# LiDAR_Lite_Interface.net
KiCad netlist of a schematic drawn in EAGLE
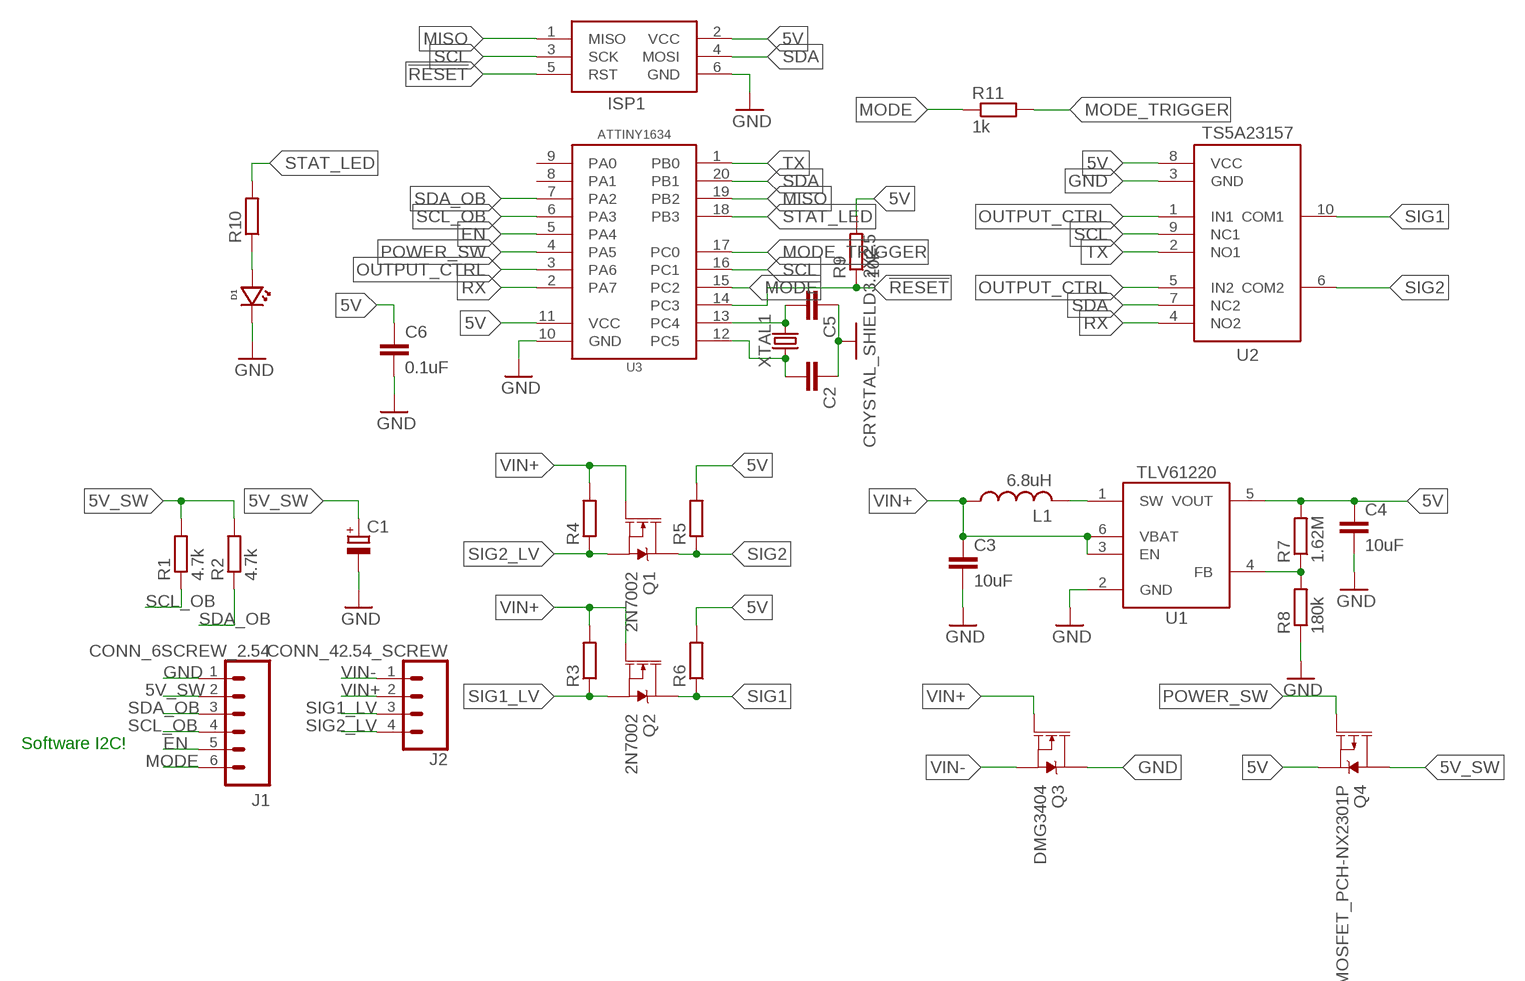
[diagram p0: schematic, sheet 1]

(export (version "E")
  (design (tool "Eeschema 10.0.6"))
  (components
    (comp (ref "C1")
      (value "CPOL-EUUW-10X10")
      (footprint "eagle-import:UW-10X10_NICHICON")
      (libsource (lib "eagle-import") (part "CPOL-EUUW-10X10"))
    )
    (comp (ref "C2")
      (value "C-EU10PFC0603")
      (footprint "eagle-import:C0603")
      (fields (field (name "MF") "Yageo") (field (name "MPN") "CC0603JRNPO9BN100CC0603JRNPO9BN100"))
      (libsource (lib "eagle-import") (part "C-EUC060310PF"))
    )
    (comp (ref "C3")
      (value "10uF")
      (footprint "eagle-import:C0805")
      (fields (field (name "MF") "Murata") (field (name "MPN") "GRM21BR61C106KE15K"))
      (libsource (lib "eagle-import") (part "C-EUC080510UF"))
    )
    (comp (ref "C4")
      (value "10uF")
      (footprint "eagle-import:C0805")
      (fields (field (name "MF") "Murata") (field (name "MPN") "GRM21BR61C106KE15K"))
      (libsource (lib "eagle-import") (part "C-EUC080510UF"))
    )
    (comp (ref "C5")
      (value "C-EU10PFC0603")
      (footprint "eagle-import:C0603")
      (fields (field (name "MF") "Yageo") (field (name "MPN") "CC0603JRNPO9BN100CC0603JRNPO9BN100"))
      (libsource (lib "eagle-import") (part "C-EUC060310PF"))
    )
    (comp (ref "C6")
      (value "0.1uF")
      (footprint "eagle-import:C0603")
      (fields (field (name "MF") "Murata") (field (name "MPN") "GCM188R71E104KA57D"))
      (libsource (lib "eagle-import") (part "C-EUC06030.1UF"))
    )
    (comp (ref "D1")
      (value "LED0603")
      (footprint "eagle-import:LED_0603")
      (libsource (lib "eagle-import") (part "LED0603"))
    )
    (comp (ref "ISP1")
      (value "AVRISP-6")
      (footprint "eagle-import:AVRISP")
      (libsource (lib "eagle-import") (part "AVRISP-6"))
    )
    (comp (ref "J1")
      (value "CONN_6SCREW_2.54")
      (footprint "eagle-import:1X06_SCREW")
      (fields (field (name "MF") "OnShore") (field (name "MPN") "OSTVN06A150"))
      (libsource (lib "eagle-import") (part "CONN_6SCREW_2.54"))
    )
    (comp (ref "J2")
      (value "CONN_42.54_SCREW")
      (footprint "eagle-import:1X04_SCREW")
      (fields (field (name "MF") "On Shore") (field (name "MPN") "OSTVN04A150"))
      (libsource (lib "eagle-import") (part "CONN_42.54_SCREW"))
    )
    (comp (ref "L1")
      (value "6.8uH")
      (footprint "eagle-import:1008")
      (fields (field (name "MF") "Wurth") (field (name "MPN") "74438323068"))
      (libsource (lib "eagle-import") (part "INDUCTOR1008"))
    )
    (comp (ref "Q1")
      (value "2N7002")
      (footprint "eagle-import:SOT23-3")
      (fields (field (name "MF") "Nexperia") (field (name "MPN") "2N7002P,215"))
      (libsource (lib "eagle-import") (part "MOSFET-NCH-2N7002P"))
    )
    (comp (ref "Q2")
      (value "2N7002")
      (footprint "eagle-import:SOT23-3")
      (fields (field (name "MF") "Nexperia") (field (name "MPN") "2N7002P,215"))
      (libsource (lib "eagle-import") (part "MOSFET-NCH-2N7002P"))
    )
    (comp (ref "Q3")
      (value "DMG3404")
      (footprint "eagle-import:SOT23-3")
      (fields (field (name "MF") "Diodes Incorporated") (field (name "MPN") "DMG3404L-7"))
      (libsource (lib "eagle-import") (part "MOSFET-NCH-DMG3404L"))
    )
    (comp (ref "Q4")
      (value "MOSFET_PCH-NX2301P")
      (footprint "eagle-import:SOT23-3")
      (fields (field (name "MF") "Nexperia") (field (name "MPN") "NX2301P,215"))
      (libsource (lib "eagle-import") (part "MOSFET_PCH-NX2301P"))
    )
    (comp (ref "R1")
      (value "4.7k")
      (footprint "eagle-import:R0603")
      (fields (field (name "MF") "Yageo") (field (name "MPN") "RC0603FR-074K7L"))
      (libsource (lib "eagle-import") (part "R-EU_R06034.7K"))
    )
    (comp (ref "R2")
      (value "4.7k")
      (footprint "eagle-import:R0603")
      (fields (field (name "MF") "Yageo") (field (name "MPN") "RC0603FR-074K7L"))
      (libsource (lib "eagle-import") (part "R-EU_R06034.7K"))
    )
    (comp (ref "R3")
      (value "R-EU_10KR0603")
      (footprint "eagle-import:R0603")
      (fields
        (field (name "MF") "Yageo")
        (field (name "MPN") "RC0603FR-0710KL")
        (field (name "VALUE_PART") "10k")
      )
      (libsource (lib "eagle-import") (part "R-EU_R060310K"))
    )
    (comp (ref "R4")
      (value "R-EU_10KR0603")
      (footprint "eagle-import:R0603")
      (fields
        (field (name "MF") "Yageo")
        (field (name "MPN") "RC0603FR-0710KL")
        (field (name "VALUE_PART") "10k")
      )
      (libsource (lib "eagle-import") (part "R-EU_R060310K"))
    )
    (comp (ref "R5")
      (value "R-EU_10KR0603")
      (footprint "eagle-import:R0603")
      (fields
        (field (name "MF") "Yageo")
        (field (name "MPN") "RC0603FR-0710KL")
        (field (name "VALUE_PART") "10k")
      )
      (libsource (lib "eagle-import") (part "R-EU_R060310K"))
    )
    (comp (ref "R6")
      (value "R-EU_10KR0603")
      (footprint "eagle-import:R0603")
      (fields
        (field (name "MF") "Yageo")
        (field (name "MPN") "RC0603FR-0710KL")
        (field (name "VALUE_PART") "10k")
      )
      (libsource (lib "eagle-import") (part "R-EU_R060310K"))
    )
    (comp (ref "R7")
      (value "1.62M")
      (footprint "eagle-import:R0603")
      (fields (field (name "MF") "Stackpole") (field (name "MPN") "RMCF0603FT1M62"))
      (libsource (lib "eagle-import") (part "R-EU_R06031.62M"))
    )
    (comp (ref "R8")
      (value "180k")
      (footprint "eagle-import:R0603")
      (fields (field (name "MF") "Panasonic") (field (name "MPN") "ERJ-3EKF1803V"))
      (libsource (lib "eagle-import") (part "R-EU_R0603180K"))
    )
    (comp (ref "R9")
      (value "10k")
      (footprint "eagle-import:R0603")
      (fields (field (name "MF") "Yageo") (field (name "MPN") "RC0603FR-0710KL"))
      (libsource (lib "eagle-import") (part "R-EU_R060310K"))
    )
    (comp (ref "R10")
      (value "R-EU_330R0603")
      (footprint "eagle-import:R0603")
      (fields
        (field (name "MF") "Yageo")
        (field (name "MPN") "RC0603FR-07330RL")
        (field (name "VALUE_PART") "330")
      )
      (libsource (lib "eagle-import") (part "R-EU_R0603330"))
    )
    (comp (ref "R11")
      (value "1k")
      (footprint "eagle-import:R0603")
      (fields (field (name "MF") "Yageo") (field (name "MPN") "AC0603FR-071KL"))
      (libsource (lib "eagle-import") (part "R-EU_R06031K"))
    )
    (comp (ref "U1")
      (value "TLV61220DBV")
      (footprint "eagle-import:DBV_R-PDSO-G6")
      (fields (field (name "MF") "TI") (field (name "MPN") "TLV61220DBVR"))
      (libsource (lib "eagle-import") (part "TLV61220DBV"))
    )
    (comp (ref "U2")
      (value "TS5A23157DGS")
      (footprint "eagle-import:DGS0010A")
      (fields (field (name "DISP") "TS5A23157") (field (name "MF") "TI") (field (name "MPN") "TS5A23157DGSR"))
      (libsource (lib "eagle-import") (part "TS5A23157DGS"))
    )
    (comp (ref "U3")
      (value "ATTINY1634SOIC")
      (footprint "eagle-import:SO-20DW")
      (fields (field (name "MF") "Atmel") (field (name "MPN") "ATTINY1634-SUR"))
      (libsource (lib "eagle-import") (part "ATTINY1634SOIC"))
    )
    (comp (ref "XTAL1")
      (value "CRYSTAL_SHIELD3.2X2.5")
      (footprint "eagle-import:CRYSTAL_3.2X2.5_4-SMD")
      (fields (field (name "MF") "Abricon") (field (name "MPN") "ABM8G-12.000MHZ-4Y-T3"))
      (libsource (lib "eagle-import") (part "CRYSTAL_SHIELD3.2X2.5"))
    )
  )
  (nets
    (net (code "1") (name "/~{RESET}") (class "Default")
      (node (ref "ISP1") (pin "5") (pinfunction "RST_5") (pintype "output"))
      (node (ref "R9") (pin "1") (pinfunction "1_1") (pintype "passive"))
      (node (ref "U3") (pin "14") (pinfunction "PC3_14") (pintype "bidirectional"))
    )
    (net (code "2") (name "5V") (class "Default")
      (node (ref "C4") (pin "1") (pinfunction "1_1") (pintype "passive"))
      (node (ref "C6") (pin "1") (pinfunction "1_1") (pintype "passive"))
      (node (ref "ISP1") (pin "2") (pinfunction "VCC_2") (pintype "power_in"))
      (node (ref "Q4") (pin "2") (pinfunction "S_2") (pintype "bidirectional"))
      (node (ref "R5") (pin "2") (pinfunction "2_2") (pintype "passive"))
      (node (ref "R6") (pin "2") (pinfunction "2_2") (pintype "passive"))
      (node (ref "R7") (pin "2") (pinfunction "2_2") (pintype "passive"))
      (node (ref "R9") (pin "2") (pinfunction "2_2") (pintype "passive"))
      (node (ref "U1") (pin "5") (pinfunction "VOUT_5") (pintype "power_in"))
      (node (ref "U2") (pin "8") (pinfunction "VCC_8") (pintype "power_in"))
      (node (ref "U3") (pin "11") (pinfunction "VCC_11") (pintype "power_in"))
    )
    (net (code "3") (name "5V_SW") (class "Default")
      (node (ref "C1") (pin "+") (pinfunction "+_+") (pintype "passive"))
      (node (ref "J1") (pin "2") (pinfunction "2_2") (pintype "passive"))
      (node (ref "Q4") (pin "3") (pinfunction "D_3") (pintype "bidirectional"))
      (node (ref "R1") (pin "2") (pinfunction "2_2") (pintype "passive"))
      (node (ref "R2") (pin "2") (pinfunction "2_2") (pintype "passive"))
    )
    (net (code "4") (name "EN") (class "Default")
      (node (ref "J1") (pin "5") (pinfunction "5_5") (pintype "passive"))
      (node (ref "U3") (pin "5") (pinfunction "PA4_5") (pintype "bidirectional"))
    )
    (net (code "5") (name "GND") (class "Default")
      (node (ref "C1") (pin "-") (pinfunction "-_-") (pintype "passive"))
      (node (ref "C2") (pin "1") (pinfunction "1_1") (pintype "passive"))
      (node (ref "C3") (pin "2") (pinfunction "2_2") (pintype "passive"))
      (node (ref "C4") (pin "2") (pinfunction "2_2") (pintype "passive"))
      (node (ref "C5") (pin "1") (pinfunction "1_1") (pintype "passive"))
      (node (ref "C6") (pin "2") (pinfunction "2_2") (pintype "passive"))
      (node (ref "D1") (pin "CATHODE") (pinfunction "CATHODE_CATHODE") (pintype "power_in"))
      (node (ref "ISP1") (pin "6") (pinfunction "GND_6") (pintype "power_in"))
      (node (ref "J1") (pin "1") (pinfunction "1_1") (pintype "passive"))
      (node (ref "Q3") (pin "3") (pinfunction "D_3") (pintype "bidirectional"))
      (node (ref "R8") (pin "1") (pinfunction "1_1") (pintype "passive"))
      (node (ref "U1") (pin "2") (pinfunction "GND_2") (pintype "power_in"))
      (node (ref "U2") (pin "3") (pinfunction "GND_3") (pintype "power_in"))
      (node (ref "U3") (pin "10") (pinfunction "GND_10") (pintype "power_in"))
      (node (ref "XTAL1") (pin "2") (pinfunction "GND_2") (pintype "power_in"))
      (node (ref "XTAL1") (pin "4") (pinfunction "GND_4") (pintype "power_in"))
    )
    (net (code "6") (name "MISO") (class "Default")
      (node (ref "ISP1") (pin "1") (pinfunction "MISO_1") (pintype "input"))
      (node (ref "U3") (pin "19") (pinfunction "PB2_19") (pintype "bidirectional"))
    )
    (net (code "7") (name "MODE") (class "Default")
      (node (ref "J1") (pin "6") (pinfunction "6_6") (pintype "passive"))
      (node (ref "R11") (pin "1") (pinfunction "1_1") (pintype "passive"))
      (node (ref "U3") (pin "15") (pinfunction "PC2_15") (pintype "bidirectional"))
    )
    (net (code "8") (name "MODE_TRIGGER") (class "Default")
      (node (ref "R11") (pin "2") (pinfunction "2_2") (pintype "passive"))
      (node (ref "U3") (pin "17") (pinfunction "PC0_17") (pintype "bidirectional"))
    )
    (net (code "9") (name "Net-(D1-PadANODE)") (class "Default")
      (node (ref "D1") (pin "ANODE") (pinfunction "ANODE_ANODE") (pintype "power_in"))
      (node (ref "R10") (pin "1") (pinfunction "1_1") (pintype "passive"))
    )
    (net (code "10") (name "Net-(U1-FB)") (class "Default")
      (node (ref "R7") (pin "1") (pinfunction "1_1") (pintype "passive"))
      (node (ref "R8") (pin "2") (pinfunction "2_2") (pintype "passive"))
      (node (ref "U1") (pin "4") (pinfunction "FB_4") (pintype "input"))
    )
    (net (code "11") (name "Net-(U1-SW)") (class "Default")
      (node (ref "L1") (pin "2") (pinfunction "2_2") (pintype "passive"))
      (node (ref "U1") (pin "1") (pinfunction "SW_1") (pintype "power_in"))
    )
    (net (code "12") (name "Net-(U3-PC4)") (class "Default")
      (node (ref "C5") (pin "2") (pinfunction "2_2") (pintype "passive"))
      (node (ref "U3") (pin "13") (pinfunction "PC4_13") (pintype "bidirectional"))
      (node (ref "XTAL1") (pin "3") (pinfunction "2_3") (pintype "passive"))
    )
    (net (code "13") (name "Net-(U3-PC5)") (class "Default")
      (node (ref "C2") (pin "2") (pinfunction "2_2") (pintype "passive"))
      (node (ref "U3") (pin "12") (pinfunction "PC5_12") (pintype "bidirectional"))
      (node (ref "XTAL1") (pin "1") (pinfunction "1_1") (pintype "passive"))
    )
    (net (code "14") (name "OUTPUT_CTRL") (class "Default")
      (node (ref "U2") (pin "1") (pinfunction "IN1_1") (pintype "input"))
      (node (ref "U2") (pin "5") (pinfunction "IN2_5") (pintype "input"))
      (node (ref "U3") (pin "3") (pinfunction "PA6_3") (pintype "bidirectional"))
    )
    (net (code "15") (name "POWER_SW") (class "Default")
      (node (ref "Q4") (pin "1") (pinfunction "G_1") (pintype "bidirectional"))
      (node (ref "U3") (pin "4") (pinfunction "PA5_4") (pintype "bidirectional"))
    )
    (net (code "16") (name "RX") (class "Default")
      (node (ref "U2") (pin "4") (pinfunction "NO2_4") (pintype "bidirectional"))
      (node (ref "U3") (pin "2") (pinfunction "PA7_2") (pintype "bidirectional"))
    )
    (net (code "17") (name "SCL") (class "Default")
      (node (ref "ISP1") (pin "3") (pinfunction "SCK_3") (pintype "output"))
      (node (ref "U2") (pin "9") (pinfunction "NC1_9") (pintype "bidirectional"))
      (node (ref "U3") (pin "16") (pinfunction "PC1_16") (pintype "bidirectional"))
    )
    (net (code "18") (name "SCL_OB") (class "Default")
      (node (ref "J1") (pin "4") (pinfunction "4_4") (pintype "passive"))
      (node (ref "R1") (pin "1") (pinfunction "1_1") (pintype "passive"))
      (node (ref "U3") (pin "6") (pinfunction "PA3_6") (pintype "bidirectional"))
    )
    (net (code "19") (name "SDA") (class "Default")
      (node (ref "ISP1") (pin "4") (pinfunction "MOSI_4") (pintype "output"))
      (node (ref "U2") (pin "7") (pinfunction "NC2_7") (pintype "bidirectional"))
      (node (ref "U3") (pin "20") (pinfunction "PB1_20") (pintype "bidirectional"))
    )
    (net (code "20") (name "SDA_OB") (class "Default")
      (node (ref "J1") (pin "3") (pinfunction "3_3") (pintype "passive"))
      (node (ref "R2") (pin "1") (pinfunction "1_1") (pintype "passive"))
      (node (ref "U3") (pin "7") (pinfunction "PA2_7") (pintype "bidirectional"))
    )
    (net (code "21") (name "SIG1") (class "Default")
      (node (ref "Q2") (pin "3") (pinfunction "D_3") (pintype "bidirectional"))
      (node (ref "R6") (pin "1") (pinfunction "1_1") (pintype "passive"))
      (node (ref "U2") (pin "10") (pinfunction "COM1_10") (pintype "bidirectional"))
    )
    (net (code "22") (name "SIG1_LV") (class "Default")
      (node (ref "J2") (pin "3") (pinfunction "3_3") (pintype "passive"))
      (node (ref "Q2") (pin "2") (pinfunction "S_2") (pintype "bidirectional"))
      (node (ref "R3") (pin "1") (pinfunction "1_1") (pintype "passive"))
    )
    (net (code "23") (name "SIG2") (class "Default")
      (node (ref "Q1") (pin "3") (pinfunction "D_3") (pintype "bidirectional"))
      (node (ref "R5") (pin "1") (pinfunction "1_1") (pintype "passive"))
      (node (ref "U2") (pin "6") (pinfunction "COM2_6") (pintype "bidirectional"))
    )
    (net (code "24") (name "SIG2_LV") (class "Default")
      (node (ref "J2") (pin "4") (pinfunction "4_4") (pintype "passive"))
      (node (ref "Q1") (pin "2") (pinfunction "S_2") (pintype "bidirectional"))
      (node (ref "R4") (pin "1") (pinfunction "1_1") (pintype "passive"))
    )
    (net (code "25") (name "STAT_LED") (class "Default")
      (node (ref "R10") (pin "2") (pinfunction "2_2") (pintype "passive"))
      (node (ref "U3") (pin "18") (pinfunction "PB3_18") (pintype "bidirectional"))
    )
    (net (code "26") (name "TX") (class "Default")
      (node (ref "U2") (pin "2") (pinfunction "NO1_2") (pintype "bidirectional"))
      (node (ref "U3") (pin "1") (pinfunction "PB0_1") (pintype "bidirectional"))
    )
    (net (code "27") (name "VIN+") (class "Default")
      (node (ref "C3") (pin "1") (pinfunction "1_1") (pintype "passive"))
      (node (ref "J2") (pin "2") (pinfunction "2_2") (pintype "passive"))
      (node (ref "L1") (pin "1") (pinfunction "1_1") (pintype "passive"))
      (node (ref "Q1") (pin "1") (pinfunction "G_1") (pintype "bidirectional"))
      (node (ref "Q2") (pin "1") (pinfunction "G_1") (pintype "bidirectional"))
      (node (ref "Q3") (pin "1") (pinfunction "G_1") (pintype "bidirectional"))
      (node (ref "R3") (pin "2") (pinfunction "2_2") (pintype "passive"))
      (node (ref "R4") (pin "2") (pinfunction "2_2") (pintype "passive"))
      (node (ref "U1") (pin "3") (pinfunction "EN_3") (pintype "input"))
      (node (ref "U1") (pin "6") (pinfunction "VBAT_6") (pintype "power_in"))
    )
    (net (code "28") (name "VIN-") (class "Default")
      (node (ref "J2") (pin "1") (pinfunction "1_1") (pintype "passive"))
      (node (ref "Q3") (pin "2") (pinfunction "S_2") (pintype "bidirectional"))
    )
    (net (code "29") (name "unconnected-(U3-PA0-Pad9)") (class "Default")
      (node (ref "U3") (pin "9") (pinfunction "PA0_9") (pintype "bidirectional"))
    )
    (net (code "30") (name "unconnected-(U3-PA1-Pad8)") (class "Default")
      (node (ref "U3") (pin "8") (pinfunction "PA1_8") (pintype "bidirectional"))
    )
  )
)
